# 07_-_POWER_SUPPLY.net
KiCad netlist of a schematic drawn in Altium Designer
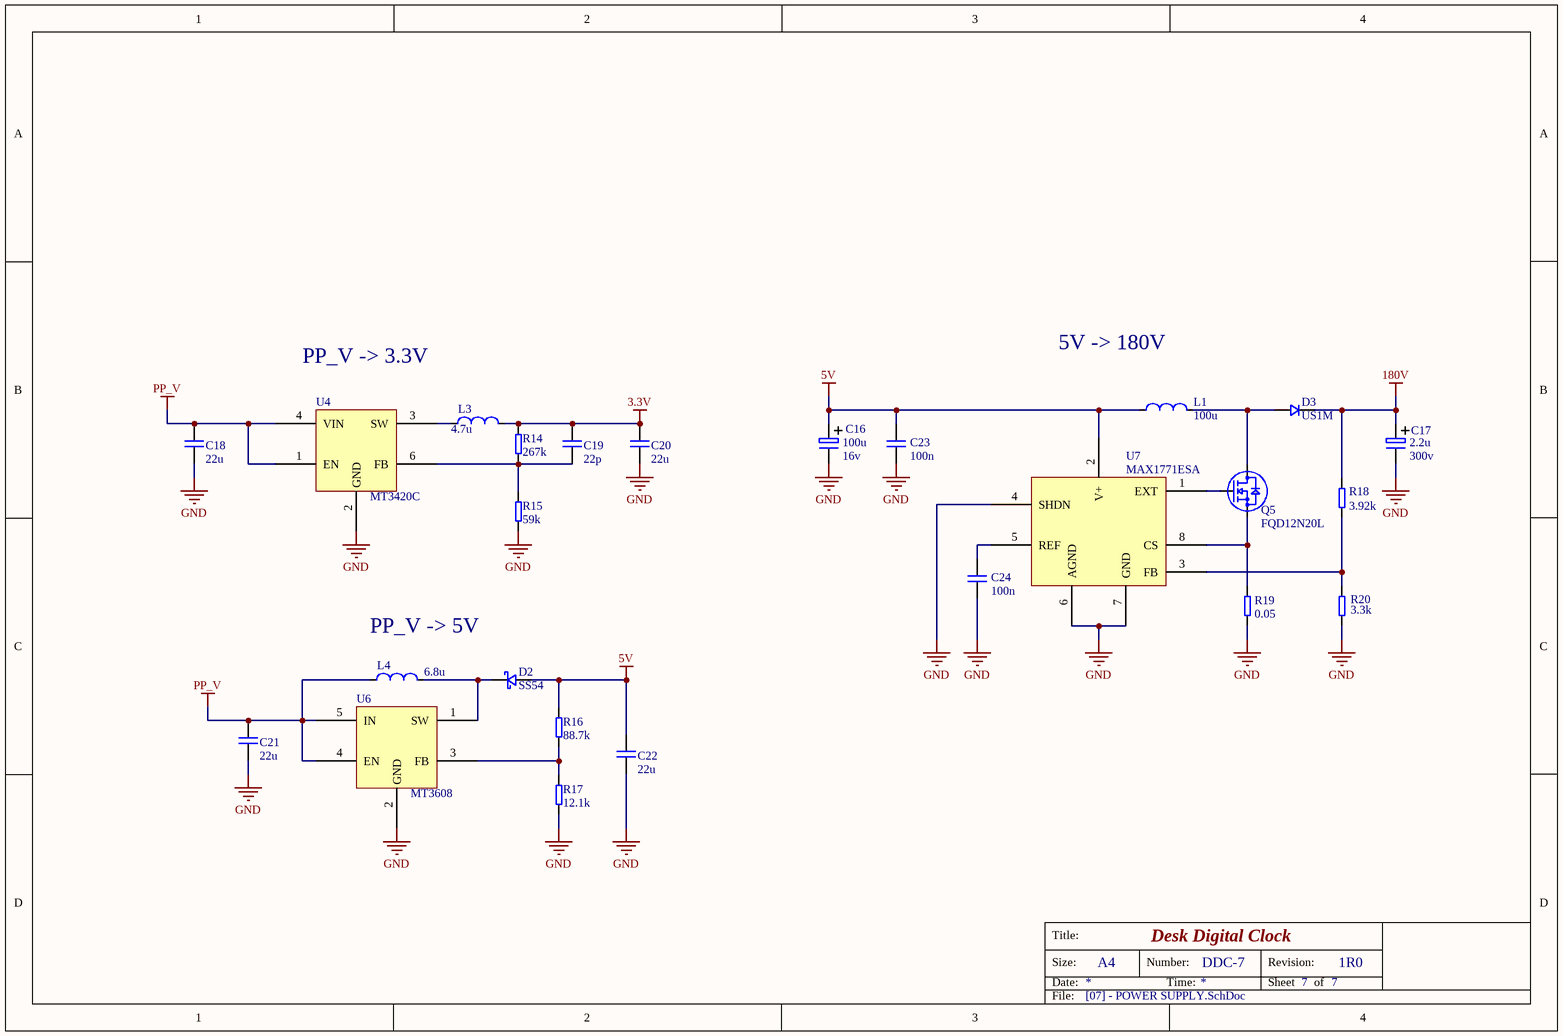
[diagram p0: [07] - POWER SUPPLY.SchDoc]

(export (version "E")
  (design (tool "Eeschema 10.0.6"))
  (components
    (comp (ref "C16")
      (value "100u")
      (footprint "CAPM3216X18N_TANTAL_E")
      (description "CAPACITOR")
      (fields (field (name "VOLTAGE") "16v"))
      (libsource (lib "1") (part "Cap_p"))
    )
    (comp (ref "C17")
      (value "2.2u")
      (footprint "CAP_8X10.2")
      (description "CAPACITOR")
      (fields (field (name "VOLTAGE") "300v"))
      (libsource (lib "1") (part "Cap_p"))
    )
    (comp (ref "C18")
      (value "22u")
      (footprint "C1210")
      (description "CAPACITOR")
      (libsource (lib "1") (part "Cap"))
    )
    (comp (ref "C19")
      (value "22p")
      (footprint "C0603")
      (description "CAPACITOR")
      (libsource (lib "1") (part "Cap"))
    )
    (comp (ref "C20")
      (value "22u")
      (footprint "C1210")
      (description "CAPACITOR")
      (libsource (lib "1") (part "Cap"))
    )
    (comp (ref "C21")
      (value "22u")
      (footprint "C1210")
      (description "CAPACITOR")
      (libsource (lib "1") (part "Cap"))
    )
    (comp (ref "C22")
      (value "22u")
      (footprint "C1210")
      (description "CAPACITOR")
      (libsource (lib "1") (part "Cap"))
    )
    (comp (ref "C23")
      (value "100n")
      (footprint "C0603")
      (description "CAPACITOR")
      (libsource (lib "1") (part "Cap"))
    )
    (comp (ref "C24")
      (value "100n")
      (footprint "C0603")
      (description "CAPACITOR")
      (libsource (lib "1") (part "Cap"))
    )
    (comp (ref "D2")
      (value "~")
      (footprint "DIOM6959X26N-SS54")
      (description "Diode Shottky")
      (fields (field (name "P/N") "SS54"))
      (libsource (lib "1") (part "Diode_Shottky"))
    )
    (comp (ref "D3")
      (value "~")
      (footprint "DO-214AC(SMA)")
      (description "1.0A SURFACE MOUNT ULTRA-FAST RECTIFIER")
      (fields (field (name "MANUFACTURER") "Vishay") (field (name "P/N") "US1M"))
      (libsource (lib "1") (part "US1M"))
    )
    (comp (ref "L1")
      (value "100u")
      (footprint "CD127-IND")
      (description "INDUCTOR")
      (libsource (lib "1") (part "Ind"))
    )
    (comp (ref "L3")
      (value "4.7u")
      (footprint "CDRH5D16")
      (description "INDUCTOR")
      (libsource (lib "1") (part "Ind"))
    )
    (comp (ref "L4")
      (value "6.8u")
      (footprint "CDRH5D16")
      (description "INDUCTOR")
      (libsource (lib "1") (part "Ind"))
    )
    (comp (ref "Q5")
      (value "FQD12N20L")
      (footprint "DPAK-fqd12n20l")
      (description "n-Channel QFET MOSFET 200V 9A 280mOhm")
      (fields (field (name "MANUFACTURER") "Fairchild Semiconductor"))
      (libsource (lib "1") (part "FQD12N20L"))
    )
    (comp (ref "R14")
      (value "267k")
      (footprint "R0603")
      (description "RESISTOR")
      (libsource (lib "1") (part "Res"))
    )
    (comp (ref "R15")
      (value "59k")
      (footprint "R0603")
      (description "RESISTOR")
      (libsource (lib "1") (part "Res"))
    )
    (comp (ref "R16")
      (value "88.7k")
      (footprint "R0603")
      (description "RESISTOR")
      (libsource (lib "1") (part "Res"))
    )
    (comp (ref "R17")
      (value "12.1k")
      (footprint "R0603")
      (description "RESISTOR")
      (libsource (lib "1") (part "Res"))
    )
    (comp (ref "R18")
      (value "3.92k")
      (footprint "R0603")
      (description "RESISTOR")
      (libsource (lib "1") (part "Res"))
    )
    (comp (ref "R19")
      (value "0.05")
      (footprint "R1206")
      (description "RESISTOR")
      (libsource (lib "1") (part "Res"))
    )
    (comp (ref "R20")
      (value "3.3k")
      (footprint "R0603")
      (description "RESISTOR")
      (libsource (lib "1") (part "Res"))
    )
    (comp (ref "U4")
      (value "MT3420C")
      (footprint "SOT23-6-MT3420C")
      (description "2A 2.3-6V Input 1.5MHz Synchronous Step-Down Converter")
      (fields (field (name "MANUFACTURER") "Aerosemi"))
      (libsource (lib "1") (part "MT3420C"))
    )
    (comp (ref "U6")
      (value "MT3608")
      (footprint "SOT23-6-MT3420C")
      (description "High Efficiency 1.2MHz 2A Step Up Converter")
      (fields (field (name "MANUFACTURER") "Aerosemi"))
      (libsource (lib "1") (part "MT3608"))
    )
    (comp (ref "U7")
      (value "MAX1771ESA")
      (footprint "MAX1771ESA")
      (description "12V or Adjustable, High-Efficiency,\r\nLow IQ, Step-Up DC-DC Controller")
      (fields (field (name "MANUFACTURER") "Maxim"))
      (libsource (lib "1") (part "MAX1771ESA"))
    )
  )
  (nets
    (net (code "1") (name "3.3V") (class "Default")
      (node (ref "C19") (pin "2") (pinfunction "2_2") (pintype "passive"))
      (node (ref "C20") (pin "2") (pinfunction "2_2") (pintype "passive"))
      (node (ref "L3") (pin "2") (pinfunction "2_2") (pintype "passive"))
      (node (ref "R14") (pin "2") (pinfunction "2_2") (pintype "passive"))
    )
    (net (code "2") (name "5V") (class "Default")
      (node (ref "C16") (pin "1") (pinfunction "1_1") (pintype "passive"))
      (node (ref "C22") (pin "2") (pinfunction "2_2") (pintype "passive"))
      (node (ref "C23") (pin "2") (pinfunction "2_2") (pintype "passive"))
      (node (ref "D2") (pin "2") (pinfunction "2_2") (pintype "passive"))
      (node (ref "L1") (pin "1") (pinfunction "1_1") (pintype "passive"))
      (node (ref "R16") (pin "2") (pinfunction "2_2") (pintype "passive"))
      (node (ref "U7") (pin "2") (pinfunction "V+_2") (pintype "passive"))
    )
    (net (code "3") (name "180V") (class "Default")
      (node (ref "C17") (pin "1") (pinfunction "1_1") (pintype "passive"))
      (node (ref "D3") (pin "1") (pinfunction "1_1") (pintype "passive"))
      (node (ref "R18") (pin "2") (pinfunction "2_2") (pintype "passive"))
    )
    (net (code "4") (name "GND") (class "Default")
      (node (ref "C16") (pin "2") (pinfunction "2_2") (pintype "passive"))
      (node (ref "C17") (pin "2") (pinfunction "2_2") (pintype "passive"))
      (node (ref "C18") (pin "1") (pinfunction "1_1") (pintype "passive"))
      (node (ref "C20") (pin "1") (pinfunction "1_1") (pintype "passive"))
      (node (ref "C21") (pin "1") (pinfunction "1_1") (pintype "passive"))
      (node (ref "C22") (pin "1") (pinfunction "1_1") (pintype "passive"))
      (node (ref "C23") (pin "1") (pinfunction "1_1") (pintype "passive"))
      (node (ref "C24") (pin "1") (pinfunction "1_1") (pintype "passive"))
      (node (ref "R15") (pin "1") (pinfunction "1_1") (pintype "passive"))
      (node (ref "R17") (pin "1") (pinfunction "1_1") (pintype "passive"))
      (node (ref "R19") (pin "1") (pinfunction "1_1") (pintype "passive"))
      (node (ref "R20") (pin "1") (pinfunction "1_1") (pintype "passive"))
      (node (ref "U4") (pin "2") (pinfunction "GND_2") (pintype "passive"))
      (node (ref "U6") (pin "2") (pinfunction "GND_2") (pintype "passive"))
      (node (ref "U7") (pin "4") (pinfunction "SHDN_4") (pintype "passive"))
      (node (ref "U7") (pin "6") (pinfunction "AGND_6") (pintype "passive"))
      (node (ref "U7") (pin "7") (pinfunction "GND_7") (pintype "passive"))
    )
    (net (code "5") (name "Net-(D3-Pad2)") (class "Default")
      (node (ref "D3") (pin "2") (pinfunction "2_2") (pintype "passive"))
      (node (ref "L1") (pin "2") (pinfunction "2_2") (pintype "passive"))
      (node (ref "Q5") (pin "D") (pinfunction "D_D") (pintype "passive"))
    )
    (net (code "6") (name "Net-(U4-FB)") (class "Default")
      (node (ref "C19") (pin "1") (pinfunction "1_1") (pintype "passive"))
      (node (ref "R14") (pin "1") (pinfunction "1_1") (pintype "passive"))
      (node (ref "R15") (pin "2") (pinfunction "2_2") (pintype "passive"))
      (node (ref "U4") (pin "6") (pinfunction "FB_6") (pintype "passive"))
    )
    (net (code "7") (name "Net-(U4-SW)") (class "Default")
      (node (ref "L3") (pin "1") (pinfunction "1_1") (pintype "passive"))
      (node (ref "U4") (pin "3") (pinfunction "SW_3") (pintype "passive"))
    )
    (net (code "8") (name "Net-(U6-FB)") (class "Default")
      (node (ref "R16") (pin "1") (pinfunction "1_1") (pintype "passive"))
      (node (ref "R17") (pin "2") (pinfunction "2_2") (pintype "passive"))
      (node (ref "U6") (pin "3") (pinfunction "FB_3") (pintype "passive"))
    )
    (net (code "9") (name "Net-(U6-SW)") (class "Default")
      (node (ref "D2") (pin "1") (pinfunction "1_1") (pintype "passive"))
      (node (ref "L4") (pin "2") (pinfunction "2_2") (pintype "passive"))
      (node (ref "U6") (pin "1") (pinfunction "SW_1") (pintype "passive"))
    )
    (net (code "10") (name "Net-(U7-CS)") (class "Default")
      (node (ref "Q5") (pin "S") (pinfunction "S_S") (pintype "passive"))
      (node (ref "R19") (pin "2") (pinfunction "2_2") (pintype "passive"))
      (node (ref "U7") (pin "8") (pinfunction "CS_8") (pintype "passive"))
    )
    (net (code "11") (name "Net-(U7-EXT)") (class "Default")
      (node (ref "Q5") (pin "G") (pinfunction "G_G") (pintype "passive"))
      (node (ref "U7") (pin "1") (pinfunction "EXT_1") (pintype "passive"))
    )
    (net (code "12") (name "Net-(U7-FB)") (class "Default")
      (node (ref "R18") (pin "1") (pinfunction "1_1") (pintype "passive"))
      (node (ref "R20") (pin "2") (pinfunction "2_2") (pintype "passive"))
      (node (ref "U7") (pin "3") (pinfunction "FB_3") (pintype "passive"))
    )
    (net (code "13") (name "Net-(U7-REF)") (class "Default")
      (node (ref "C24") (pin "2") (pinfunction "2_2") (pintype "passive"))
      (node (ref "U7") (pin "5") (pinfunction "REF_5") (pintype "passive"))
    )
    (net (code "14") (name "PP_V") (class "Default")
      (node (ref "C18") (pin "2") (pinfunction "2_2") (pintype "passive"))
      (node (ref "C21") (pin "2") (pinfunction "2_2") (pintype "passive"))
      (node (ref "L4") (pin "1") (pinfunction "1_1") (pintype "passive"))
      (node (ref "U4") (pin "1") (pinfunction "EN_1") (pintype "passive"))
      (node (ref "U4") (pin "4") (pinfunction "VIN_4") (pintype "passive"))
      (node (ref "U6") (pin "4") (pinfunction "EN_4") (pintype "passive"))
      (node (ref "U6") (pin "5") (pinfunction "IN_5") (pintype "passive"))
    )
  )
)
